# Conn_B.net
KiCad netlist of a schematic drawn in Altium Designer
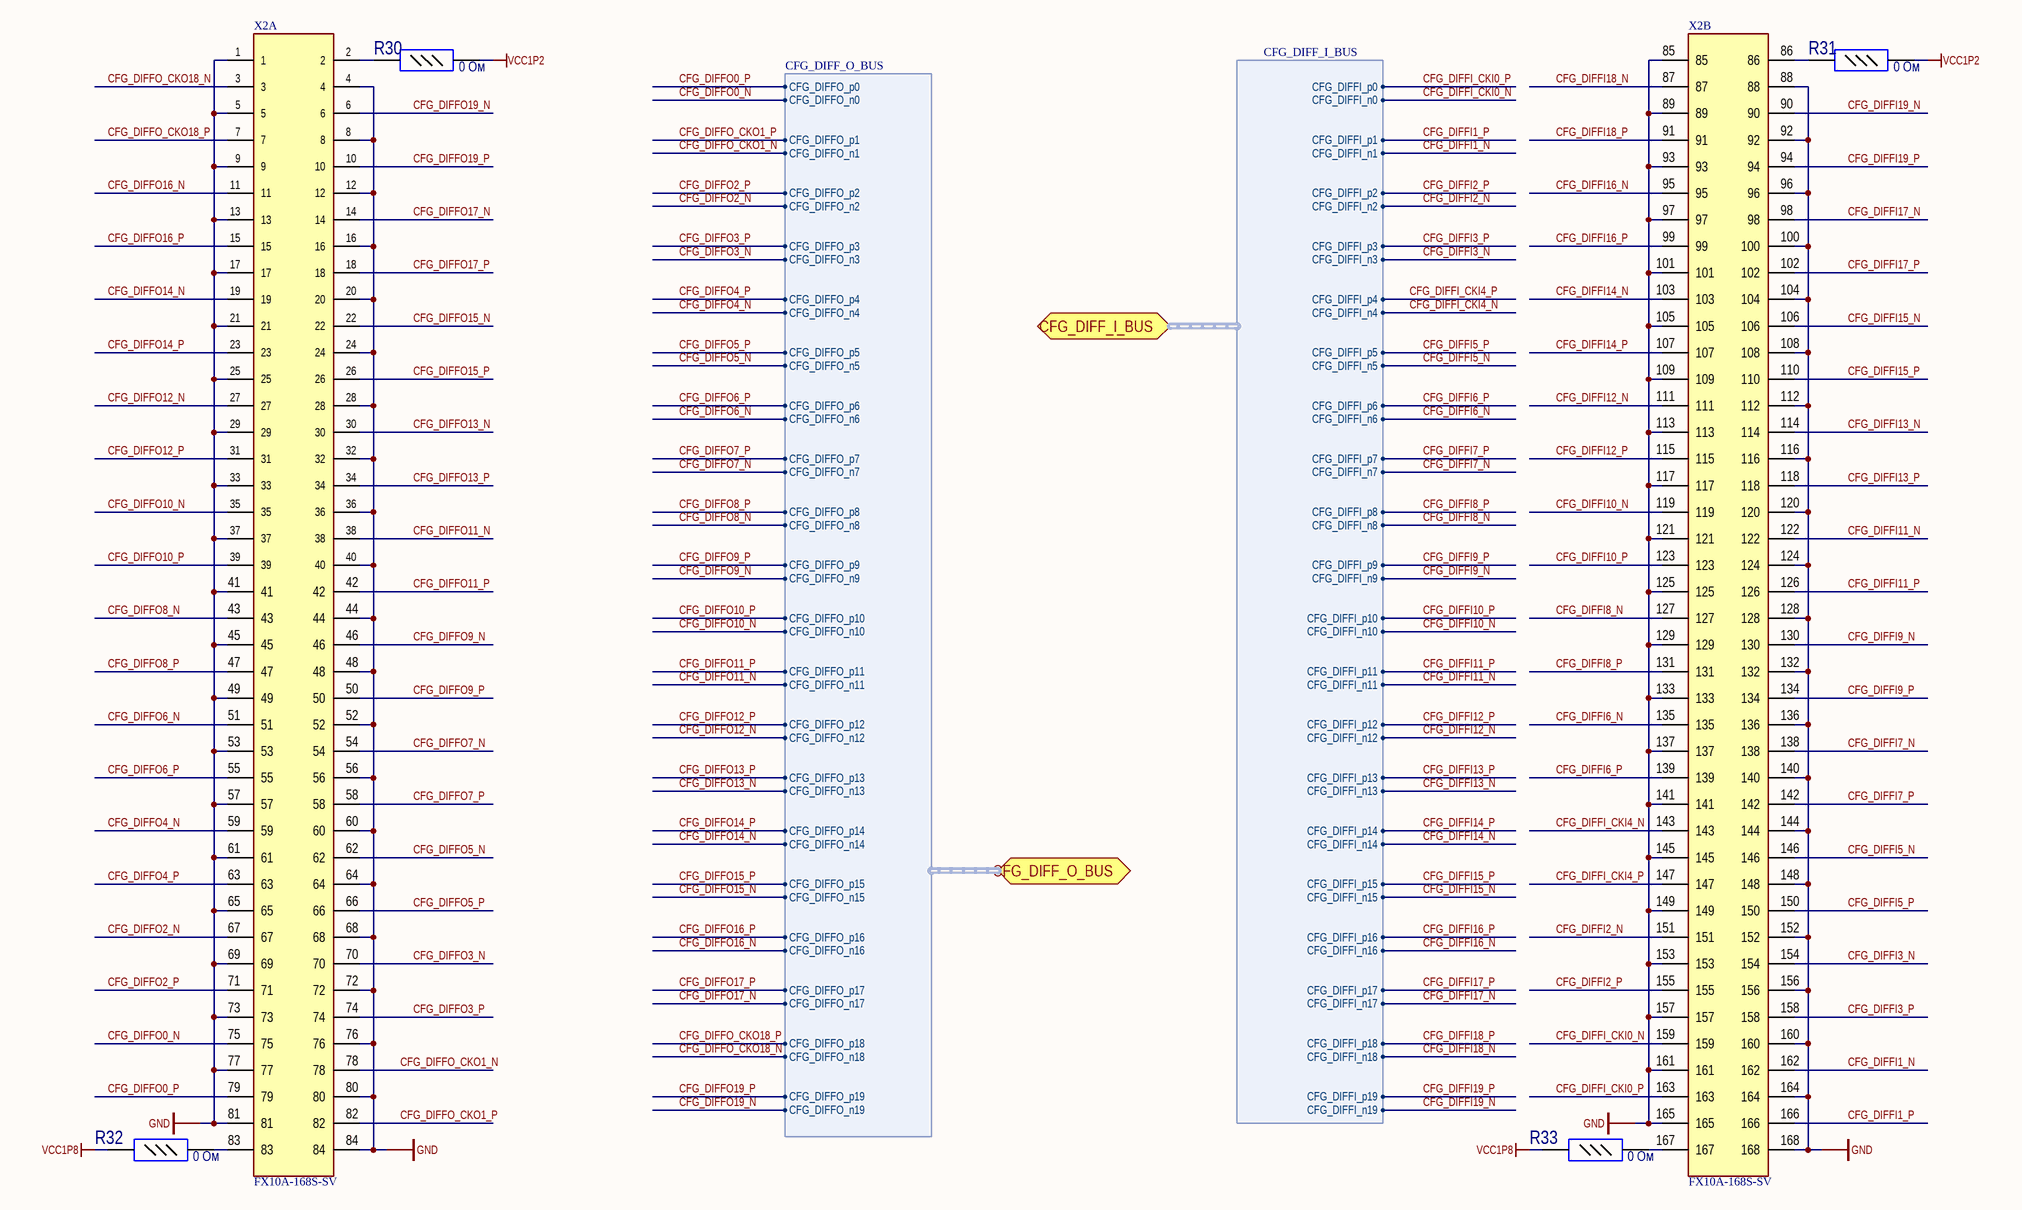
[diagram p0: Conn_B.SchDoc]

(export (version "E")
  (design (tool "Eeschema 10.0.6"))
  (components
    (comp (ref "R30")
      (value "0 Ом")
      (footprint "CR0603")
      (description "Чип резистор")
      (fields (field (name "Comment") "CR0603-0 Ом-±5%"))
      (libsource (lib "Резисторы") (part "CR0603-#-±5%"))
    )
    (comp (ref "R31")
      (value "0 Ом")
      (footprint "CR0603")
      (description "Чип резистор")
      (fields (field (name "Comment") "CR0603-0 Ом-±5%"))
      (libsource (lib "Резисторы") (part "CR0603-#-±5%"))
    )
    (comp (ref "R32")
      (value "0 Ом")
      (footprint "CR0603")
      (description "Чип резистор")
      (fields (field (name "Comment") "CR0603-0 Ом-±5%"))
      (libsource (lib "Резисторы") (part "CR0603-#-±5%"))
    )
    (comp (ref "R33")
      (value "0 Ом")
      (footprint "CR0603")
      (description "Чип резистор")
      (fields (field (name "Comment") "CR0603-0 Ом-±5%"))
      (libsource (lib "Резисторы") (part "CR0603-#-±5%"))
    )
    (comp (ref "X2")
      (value "FX10A-168S-SV")
      (footprint "FX10A-168S-SV")
      (libsource (lib "SD_IC") (part "FX10A-168S-SV"))
    )
  )
  (nets
    (net (code "3") (name "/CFG_DIFFI1_N") (class "Default")
      (node (ref "X2") (pin "162") (pinfunction "162_162") (pintype "passive"))
    )
    (net (code "4") (name "/CFG_DIFFI1_P") (class "Default")
      (node (ref "X2") (pin "166") (pinfunction "166_166") (pintype "passive"))
    )
    (net (code "5") (name "/CFG_DIFFI2_N") (class "Default")
      (node (ref "X2") (pin "151") (pinfunction "151_151") (pintype "passive"))
    )
    (net (code "6") (name "/CFG_DIFFI2_P") (class "Default")
      (node (ref "X2") (pin "155") (pinfunction "155_155") (pintype "passive"))
    )
    (net (code "7") (name "/CFG_DIFFI3_N") (class "Default")
      (node (ref "X2") (pin "154") (pinfunction "154_154") (pintype "passive"))
    )
    (net (code "8") (name "/CFG_DIFFI3_P") (class "Default")
      (node (ref "X2") (pin "158") (pinfunction "158_158") (pintype "passive"))
    )
    (net (code "9") (name "/CFG_DIFFI5_N") (class "Default")
      (node (ref "X2") (pin "146") (pinfunction "146_146") (pintype "passive"))
    )
    (net (code "10") (name "/CFG_DIFFI5_P") (class "Default")
      (node (ref "X2") (pin "150") (pinfunction "150_150") (pintype "passive"))
    )
    (net (code "11") (name "/CFG_DIFFI6_N") (class "Default")
      (node (ref "X2") (pin "135") (pinfunction "135_135") (pintype "passive"))
    )
    (net (code "12") (name "/CFG_DIFFI6_P") (class "Default")
      (node (ref "X2") (pin "139") (pinfunction "139_139") (pintype "passive"))
    )
    (net (code "13") (name "/CFG_DIFFI7_N") (class "Default")
      (node (ref "X2") (pin "138") (pinfunction "138_138") (pintype "passive"))
    )
    (net (code "14") (name "/CFG_DIFFI7_P") (class "Default")
      (node (ref "X2") (pin "142") (pinfunction "142_142") (pintype "passive"))
    )
    (net (code "15") (name "/CFG_DIFFI8_N") (class "Default")
      (node (ref "X2") (pin "127") (pinfunction "127_127") (pintype "passive"))
    )
    (net (code "16") (name "/CFG_DIFFI8_P") (class "Default")
      (node (ref "X2") (pin "131") (pinfunction "131_131") (pintype "passive"))
    )
    (net (code "17") (name "/CFG_DIFFI9_N") (class "Default")
      (node (ref "X2") (pin "130") (pinfunction "130_130") (pintype "passive"))
    )
    (net (code "18") (name "/CFG_DIFFI9_P") (class "Default")
      (node (ref "X2") (pin "134") (pinfunction "134_134") (pintype "passive"))
    )
    (net (code "19") (name "/CFG_DIFFI10_N") (class "Default")
      (node (ref "X2") (pin "119") (pinfunction "119_119") (pintype "passive"))
    )
    (net (code "20") (name "/CFG_DIFFI10_P") (class "Default")
      (node (ref "X2") (pin "123") (pinfunction "123_123") (pintype "passive"))
    )
    (net (code "21") (name "/CFG_DIFFI11_N") (class "Default")
      (node (ref "X2") (pin "122") (pinfunction "122_122") (pintype "passive"))
    )
    (net (code "22") (name "/CFG_DIFFI11_P") (class "Default")
      (node (ref "X2") (pin "126") (pinfunction "126_126") (pintype "passive"))
    )
    (net (code "23") (name "/CFG_DIFFI12_N") (class "Default")
      (node (ref "X2") (pin "111") (pinfunction "111_111") (pintype "passive"))
    )
    (net (code "24") (name "/CFG_DIFFI12_P") (class "Default")
      (node (ref "X2") (pin "115") (pinfunction "115_115") (pintype "passive"))
    )
    (net (code "25") (name "/CFG_DIFFI13_N") (class "Default")
      (node (ref "X2") (pin "114") (pinfunction "114_114") (pintype "passive"))
    )
    (net (code "26") (name "/CFG_DIFFI13_P") (class "Default")
      (node (ref "X2") (pin "118") (pinfunction "118_118") (pintype "passive"))
    )
    (net (code "27") (name "/CFG_DIFFI14_N") (class "Default")
      (node (ref "X2") (pin "103") (pinfunction "103_103") (pintype "passive"))
    )
    (net (code "28") (name "/CFG_DIFFI14_P") (class "Default")
      (node (ref "X2") (pin "107") (pinfunction "107_107") (pintype "passive"))
    )
    (net (code "29") (name "/CFG_DIFFI15_N") (class "Default")
      (node (ref "X2") (pin "106") (pinfunction "106_106") (pintype "passive"))
    )
    (net (code "30") (name "/CFG_DIFFI15_P") (class "Default")
      (node (ref "X2") (pin "110") (pinfunction "110_110") (pintype "passive"))
    )
    (net (code "31") (name "/CFG_DIFFI16_N") (class "Default")
      (node (ref "X2") (pin "95") (pinfunction "95_95") (pintype "passive"))
    )
    (net (code "32") (name "/CFG_DIFFI16_P") (class "Default")
      (node (ref "X2") (pin "99") (pinfunction "99_99") (pintype "passive"))
    )
    (net (code "33") (name "/CFG_DIFFI17_N") (class "Default")
      (node (ref "X2") (pin "98") (pinfunction "98_98") (pintype "passive"))
    )
    (net (code "34") (name "/CFG_DIFFI17_P") (class "Default")
      (node (ref "X2") (pin "102") (pinfunction "102_102") (pintype "passive"))
    )
    (net (code "35") (name "/CFG_DIFFI18_N") (class "Default")
      (node (ref "X2") (pin "87") (pinfunction "87_87") (pintype "passive"))
    )
    (net (code "36") (name "/CFG_DIFFI18_P") (class "Default")
      (node (ref "X2") (pin "91") (pinfunction "91_91") (pintype "passive"))
    )
    (net (code "37") (name "/CFG_DIFFI19_N") (class "Default")
      (node (ref "X2") (pin "90") (pinfunction "90_90") (pintype "passive"))
    )
    (net (code "38") (name "/CFG_DIFFI19_P") (class "Default")
      (node (ref "X2") (pin "94") (pinfunction "94_94") (pintype "passive"))
    )
    (net (code "39") (name "/CFG_DIFFI_CKI0_N") (class "Default")
      (node (ref "X2") (pin "159") (pinfunction "159_159") (pintype "passive"))
    )
    (net (code "40") (name "/CFG_DIFFI_CKI0_P") (class "Default")
      (node (ref "X2") (pin "163") (pinfunction "163_163") (pintype "passive"))
    )
    (net (code "41") (name "/CFG_DIFFI_CKI4_N") (class "Default")
      (node (ref "X2") (pin "143") (pinfunction "143_143") (pintype "passive"))
    )
    (net (code "42") (name "/CFG_DIFFI_CKI4_P") (class "Default")
      (node (ref "X2") (pin "147") (pinfunction "147_147") (pintype "passive"))
    )
    (net (code "43") (name "/CFG_DIFFO0_N") (class "Default")
      (node (ref "X2") (pin "75") (pinfunction "75_75") (pintype "passive"))
    )
    (net (code "44") (name "/CFG_DIFFO0_P") (class "Default")
      (node (ref "X2") (pin "79") (pinfunction "79_79") (pintype "passive"))
    )
    (net (code "45") (name "/CFG_DIFFO2_N") (class "Default")
      (node (ref "X2") (pin "67") (pinfunction "67_67") (pintype "passive"))
    )
    (net (code "46") (name "/CFG_DIFFO2_P") (class "Default")
      (node (ref "X2") (pin "71") (pinfunction "71_71") (pintype "passive"))
    )
    (net (code "47") (name "/CFG_DIFFO3_N") (class "Default")
      (node (ref "X2") (pin "70") (pinfunction "70_70") (pintype "passive"))
    )
    (net (code "48") (name "/CFG_DIFFO3_P") (class "Default")
      (node (ref "X2") (pin "74") (pinfunction "74_74") (pintype "passive"))
    )
    (net (code "49") (name "/CFG_DIFFO4_N") (class "Default")
      (node (ref "X2") (pin "59") (pinfunction "59_59") (pintype "passive"))
    )
    (net (code "50") (name "/CFG_DIFFO4_P") (class "Default")
      (node (ref "X2") (pin "63") (pinfunction "63_63") (pintype "passive"))
    )
    (net (code "51") (name "/CFG_DIFFO5_N") (class "Default")
      (node (ref "X2") (pin "62") (pinfunction "62_62") (pintype "passive"))
    )
    (net (code "52") (name "/CFG_DIFFO5_P") (class "Default")
      (node (ref "X2") (pin "66") (pinfunction "66_66") (pintype "passive"))
    )
    (net (code "53") (name "/CFG_DIFFO6_N") (class "Default")
      (node (ref "X2") (pin "51") (pinfunction "51_51") (pintype "passive"))
    )
    (net (code "54") (name "/CFG_DIFFO6_P") (class "Default")
      (node (ref "X2") (pin "55") (pinfunction "55_55") (pintype "passive"))
    )
    (net (code "55") (name "/CFG_DIFFO7_N") (class "Default")
      (node (ref "X2") (pin "54") (pinfunction "54_54") (pintype "passive"))
    )
    (net (code "56") (name "/CFG_DIFFO7_P") (class "Default")
      (node (ref "X2") (pin "58") (pinfunction "58_58") (pintype "passive"))
    )
    (net (code "57") (name "/CFG_DIFFO8_N") (class "Default")
      (node (ref "X2") (pin "43") (pinfunction "43_43") (pintype "passive"))
    )
    (net (code "58") (name "/CFG_DIFFO8_P") (class "Default")
      (node (ref "X2") (pin "47") (pinfunction "47_47") (pintype "passive"))
    )
    (net (code "59") (name "/CFG_DIFFO9_N") (class "Default")
      (node (ref "X2") (pin "46") (pinfunction "46_46") (pintype "passive"))
    )
    (net (code "60") (name "/CFG_DIFFO9_P") (class "Default")
      (node (ref "X2") (pin "50") (pinfunction "50_50") (pintype "passive"))
    )
    (net (code "61") (name "/CFG_DIFFO10_N") (class "Default")
      (node (ref "X2") (pin "35") (pinfunction "35_35") (pintype "passive"))
    )
    (net (code "62") (name "/CFG_DIFFO10_P") (class "Default")
      (node (ref "X2") (pin "39") (pinfunction "39_39") (pintype "passive"))
    )
    (net (code "63") (name "/CFG_DIFFO11_N") (class "Default")
      (node (ref "X2") (pin "38") (pinfunction "38_38") (pintype "passive"))
    )
    (net (code "64") (name "/CFG_DIFFO11_P") (class "Default")
      (node (ref "X2") (pin "42") (pinfunction "42_42") (pintype "passive"))
    )
    (net (code "65") (name "/CFG_DIFFO12_N") (class "Default")
      (node (ref "X2") (pin "27") (pinfunction "27_27") (pintype "passive"))
    )
    (net (code "66") (name "/CFG_DIFFO12_P") (class "Default")
      (node (ref "X2") (pin "31") (pinfunction "31_31") (pintype "passive"))
    )
    (net (code "67") (name "/CFG_DIFFO13_N") (class "Default")
      (node (ref "X2") (pin "30") (pinfunction "30_30") (pintype "passive"))
    )
    (net (code "68") (name "/CFG_DIFFO13_P") (class "Default")
      (node (ref "X2") (pin "34") (pinfunction "34_34") (pintype "passive"))
    )
    (net (code "69") (name "/CFG_DIFFO14_N") (class "Default")
      (node (ref "X2") (pin "19") (pinfunction "19_19") (pintype "passive"))
    )
    (net (code "70") (name "/CFG_DIFFO14_P") (class "Default")
      (node (ref "X2") (pin "23") (pinfunction "23_23") (pintype "passive"))
    )
    (net (code "71") (name "/CFG_DIFFO15_N") (class "Default")
      (node (ref "X2") (pin "22") (pinfunction "22_22") (pintype "passive"))
    )
    (net (code "72") (name "/CFG_DIFFO15_P") (class "Default")
      (node (ref "X2") (pin "26") (pinfunction "26_26") (pintype "passive"))
    )
    (net (code "73") (name "/CFG_DIFFO16_N") (class "Default")
      (node (ref "X2") (pin "11") (pinfunction "11_11") (pintype "passive"))
    )
    (net (code "74") (name "/CFG_DIFFO16_P") (class "Default")
      (node (ref "X2") (pin "15") (pinfunction "15_15") (pintype "passive"))
    )
    (net (code "75") (name "/CFG_DIFFO17_N") (class "Default")
      (node (ref "X2") (pin "14") (pinfunction "14_14") (pintype "passive"))
    )
    (net (code "76") (name "/CFG_DIFFO17_P") (class "Default")
      (node (ref "X2") (pin "18") (pinfunction "18_18") (pintype "passive"))
    )
    (net (code "77") (name "/CFG_DIFFO19_N") (class "Default")
      (node (ref "X2") (pin "6") (pinfunction "6_6") (pintype "passive"))
    )
    (net (code "78") (name "/CFG_DIFFO19_P") (class "Default")
      (node (ref "X2") (pin "10") (pinfunction "10_10") (pintype "passive"))
    )
    (net (code "79") (name "/CFG_DIFFO_CKO1_N") (class "Default")
      (node (ref "X2") (pin "78") (pinfunction "78_78") (pintype "passive"))
    )
    (net (code "80") (name "/CFG_DIFFO_CKO1_P") (class "Default")
      (node (ref "X2") (pin "82") (pinfunction "82_82") (pintype "passive"))
    )
    (net (code "81") (name "/CFG_DIFFO_CKO18_N") (class "Default")
      (node (ref "X2") (pin "3") (pinfunction "3_3") (pintype "passive"))
    )
    (net (code "82") (name "/CFG_DIFFO_CKO18_P") (class "Default")
      (node (ref "X2") (pin "7") (pinfunction "7_7") (pintype "passive"))
    )
    (net (code "85") (name "GND") (class "Default")
      (node (ref "X2") (pin "1") (pinfunction "1_1") (pintype "passive"))
      (node (ref "X2") (pin "100") (pinfunction "100_100") (pintype "passive"))
      (node (ref "X2") (pin "101") (pinfunction "101_101") (pintype "passive"))
      (node (ref "X2") (pin "104") (pinfunction "104_104") (pintype "passive"))
      (node (ref "X2") (pin "105") (pinfunction "105_105") (pintype "passive"))
      (node (ref "X2") (pin "108") (pinfunction "108_108") (pintype "passive"))
      (node (ref "X2") (pin "109") (pinfunction "109_109") (pintype "passive"))
      (node (ref "X2") (pin "112") (pinfunction "112_112") (pintype "passive"))
      (node (ref "X2") (pin "113") (pinfunction "113_113") (pintype "passive"))
      (node (ref "X2") (pin "116") (pinfunction "116_116") (pintype "passive"))
      (node (ref "X2") (pin "117") (pinfunction "117_117") (pintype "passive"))
      (node (ref "X2") (pin "12") (pinfunction "12_12") (pintype "passive"))
      (node (ref "X2") (pin "120") (pinfunction "120_120") (pintype "passive"))
      (node (ref "X2") (pin "121") (pinfunction "121_121") (pintype "passive"))
      (node (ref "X2") (pin "124") (pinfunction "124_124") (pintype "passive"))
      (node (ref "X2") (pin "125") (pinfunction "125_125") (pintype "passive"))
      (node (ref "X2") (pin "128") (pinfunction "128_128") (pintype "passive"))
      (node (ref "X2") (pin "129") (pinfunction "129_129") (pintype "passive"))
      (node (ref "X2") (pin "13") (pinfunction "13_13") (pintype "passive"))
      (node (ref "X2") (pin "132") (pinfunction "132_132") (pintype "passive"))
      (node (ref "X2") (pin "133") (pinfunction "133_133") (pintype "passive"))
      (node (ref "X2") (pin "136") (pinfunction "136_136") (pintype "passive"))
      (node (ref "X2") (pin "137") (pinfunction "137_137") (pintype "passive"))
      (node (ref "X2") (pin "140") (pinfunction "140_140") (pintype "passive"))
      (node (ref "X2") (pin "141") (pinfunction "141_141") (pintype "passive"))
      (node (ref "X2") (pin "144") (pinfunction "144_144") (pintype "passive"))
      (node (ref "X2") (pin "145") (pinfunction "145_145") (pintype "passive"))
      (node (ref "X2") (pin "148") (pinfunction "148_148") (pintype "passive"))
      (node (ref "X2") (pin "149") (pinfunction "149_149") (pintype "passive"))
      (node (ref "X2") (pin "152") (pinfunction "152_152") (pintype "passive"))
      (node (ref "X2") (pin "153") (pinfunction "153_153") (pintype "passive"))
      (node (ref "X2") (pin "156") (pinfunction "156_156") (pintype "passive"))
      (node (ref "X2") (pin "157") (pinfunction "157_157") (pintype "passive"))
      (node (ref "X2") (pin "16") (pinfunction "16_16") (pintype "passive"))
      (node (ref "X2") (pin "160") (pinfunction "160_160") (pintype "passive"))
      (node (ref "X2") (pin "161") (pinfunction "161_161") (pintype "passive"))
      (node (ref "X2") (pin "164") (pinfunction "164_164") (pintype "passive"))
      (node (ref "X2") (pin "165") (pinfunction "165_165") (pintype "passive"))
      (node (ref "X2") (pin "168") (pinfunction "168_168") (pintype "passive"))
      (node (ref "X2") (pin "17") (pinfunction "17_17") (pintype "passive"))
      (node (ref "X2") (pin "20") (pinfunction "20_20") (pintype "passive"))
      (node (ref "X2") (pin "21") (pinfunction "21_21") (pintype "passive"))
      (node (ref "X2") (pin "24") (pinfunction "24_24") (pintype "passive"))
      (node (ref "X2") (pin "25") (pinfunction "25_25") (pintype "passive"))
      (node (ref "X2") (pin "28") (pinfunction "28_28") (pintype "passive"))
      (node (ref "X2") (pin "29") (pinfunction "29_29") (pintype "passive"))
      (node (ref "X2") (pin "32") (pinfunction "32_32") (pintype "passive"))
      (node (ref "X2") (pin "33") (pinfunction "33_33") (pintype "passive"))
      (node (ref "X2") (pin "36") (pinfunction "36_36") (pintype "passive"))
      (node (ref "X2") (pin "37") (pinfunction "37_37") (pintype "passive"))
      (node (ref "X2") (pin "4") (pinfunction "4_4") (pintype "passive"))
      (node (ref "X2") (pin "40") (pinfunction "40_40") (pintype "passive"))
      (node (ref "X2") (pin "41") (pinfunction "41_41") (pintype "passive"))
      (node (ref "X2") (pin "44") (pinfunction "44_44") (pintype "passive"))
      (node (ref "X2") (pin "45") (pinfunction "45_45") (pintype "passive"))
      (node (ref "X2") (pin "48") (pinfunction "48_48") (pintype "passive"))
      (node (ref "X2") (pin "49") (pinfunction "49_49") (pintype "passive"))
      (node (ref "X2") (pin "5") (pinfunction "5_5") (pintype "passive"))
      (node (ref "X2") (pin "52") (pinfunction "52_52") (pintype "passive"))
      (node (ref "X2") (pin "53") (pinfunction "53_53") (pintype "passive"))
      (node (ref "X2") (pin "56") (pinfunction "56_56") (pintype "passive"))
      (node (ref "X2") (pin "57") (pinfunction "57_57") (pintype "passive"))
      (node (ref "X2") (pin "60") (pinfunction "60_60") (pintype "passive"))
      (node (ref "X2") (pin "61") (pinfunction "61_61") (pintype "passive"))
      (node (ref "X2") (pin "64") (pinfunction "64_64") (pintype "passive"))
      (node (ref "X2") (pin "65") (pinfunction "65_65") (pintype "passive"))
      (node (ref "X2") (pin "68") (pinfunction "68_68") (pintype "passive"))
      (node (ref "X2") (pin "69") (pinfunction "69_69") (pintype "passive"))
      (node (ref "X2") (pin "72") (pinfunction "72_72") (pintype "passive"))
      (node (ref "X2") (pin "73") (pinfunction "73_73") (pintype "passive"))
      (node (ref "X2") (pin "76") (pinfunction "76_76") (pintype "passive"))
      (node (ref "X2") (pin "77") (pinfunction "77_77") (pintype "passive"))
      (node (ref "X2") (pin "8") (pinfunction "8_8") (pintype "passive"))
      (node (ref "X2") (pin "80") (pinfunction "80_80") (pintype "passive"))
      (node (ref "X2") (pin "81") (pinfunction "81_81") (pintype "passive"))
      (node (ref "X2") (pin "84") (pinfunction "84_84") (pintype "passive"))
      (node (ref "X2") (pin "85") (pinfunction "85_85") (pintype "passive"))
      (node (ref "X2") (pin "88") (pinfunction "88_88") (pintype "passive"))
      (node (ref "X2") (pin "89") (pinfunction "89_89") (pintype "passive"))
      (node (ref "X2") (pin "9") (pinfunction "9_9") (pintype "passive"))
      (node (ref "X2") (pin "92") (pinfunction "92_92") (pintype "passive"))
      (node (ref "X2") (pin "93") (pinfunction "93_93") (pintype "passive"))
      (node (ref "X2") (pin "96") (pinfunction "96_96") (pintype "passive"))
      (node (ref "X2") (pin "97") (pinfunction "97_97") (pintype "passive"))
    )
    (net (code "86") (name "Net-(R30-+)") (class "Default")
      (node (ref "R30") (pin "1") (pinfunction "+_1") (pintype "passive"))
      (node (ref "X2") (pin "2") (pinfunction "2_2") (pintype "passive"))
    )
    (net (code "87") (name "Net-(R31-+)") (class "Default")
      (node (ref "R31") (pin "1") (pinfunction "+_1") (pintype "passive"))
      (node (ref "X2") (pin "86") (pinfunction "86_86") (pintype "passive"))
    )
    (net (code "88") (name "Net-(R32--)") (class "Default")
      (node (ref "R32") (pin "2") (pinfunction "-_2") (pintype "passive"))
      (node (ref "X2") (pin "83") (pinfunction "83_83") (pintype "passive"))
    )
    (net (code "89") (name "Net-(R33--)") (class "Default")
      (node (ref "R33") (pin "2") (pinfunction "-_2") (pintype "passive"))
      (node (ref "X2") (pin "167") (pinfunction "167_167") (pintype "passive"))
    )
    (net (code "90") (name "VCC1P2") (class "Default")
      (node (ref "R30") (pin "2") (pinfunction "-_2") (pintype "passive"))
      (node (ref "R31") (pin "2") (pinfunction "-_2") (pintype "passive"))
    )
    (net (code "91") (name "VCC1P8") (class "Default")
      (node (ref "R32") (pin "1") (pinfunction "+_1") (pintype "passive"))
      (node (ref "R33") (pin "1") (pinfunction "+_1") (pintype "passive"))
    )
  )
)
